# 1Coil.net
KiCad netlist of a schematic drawn in EAGLE
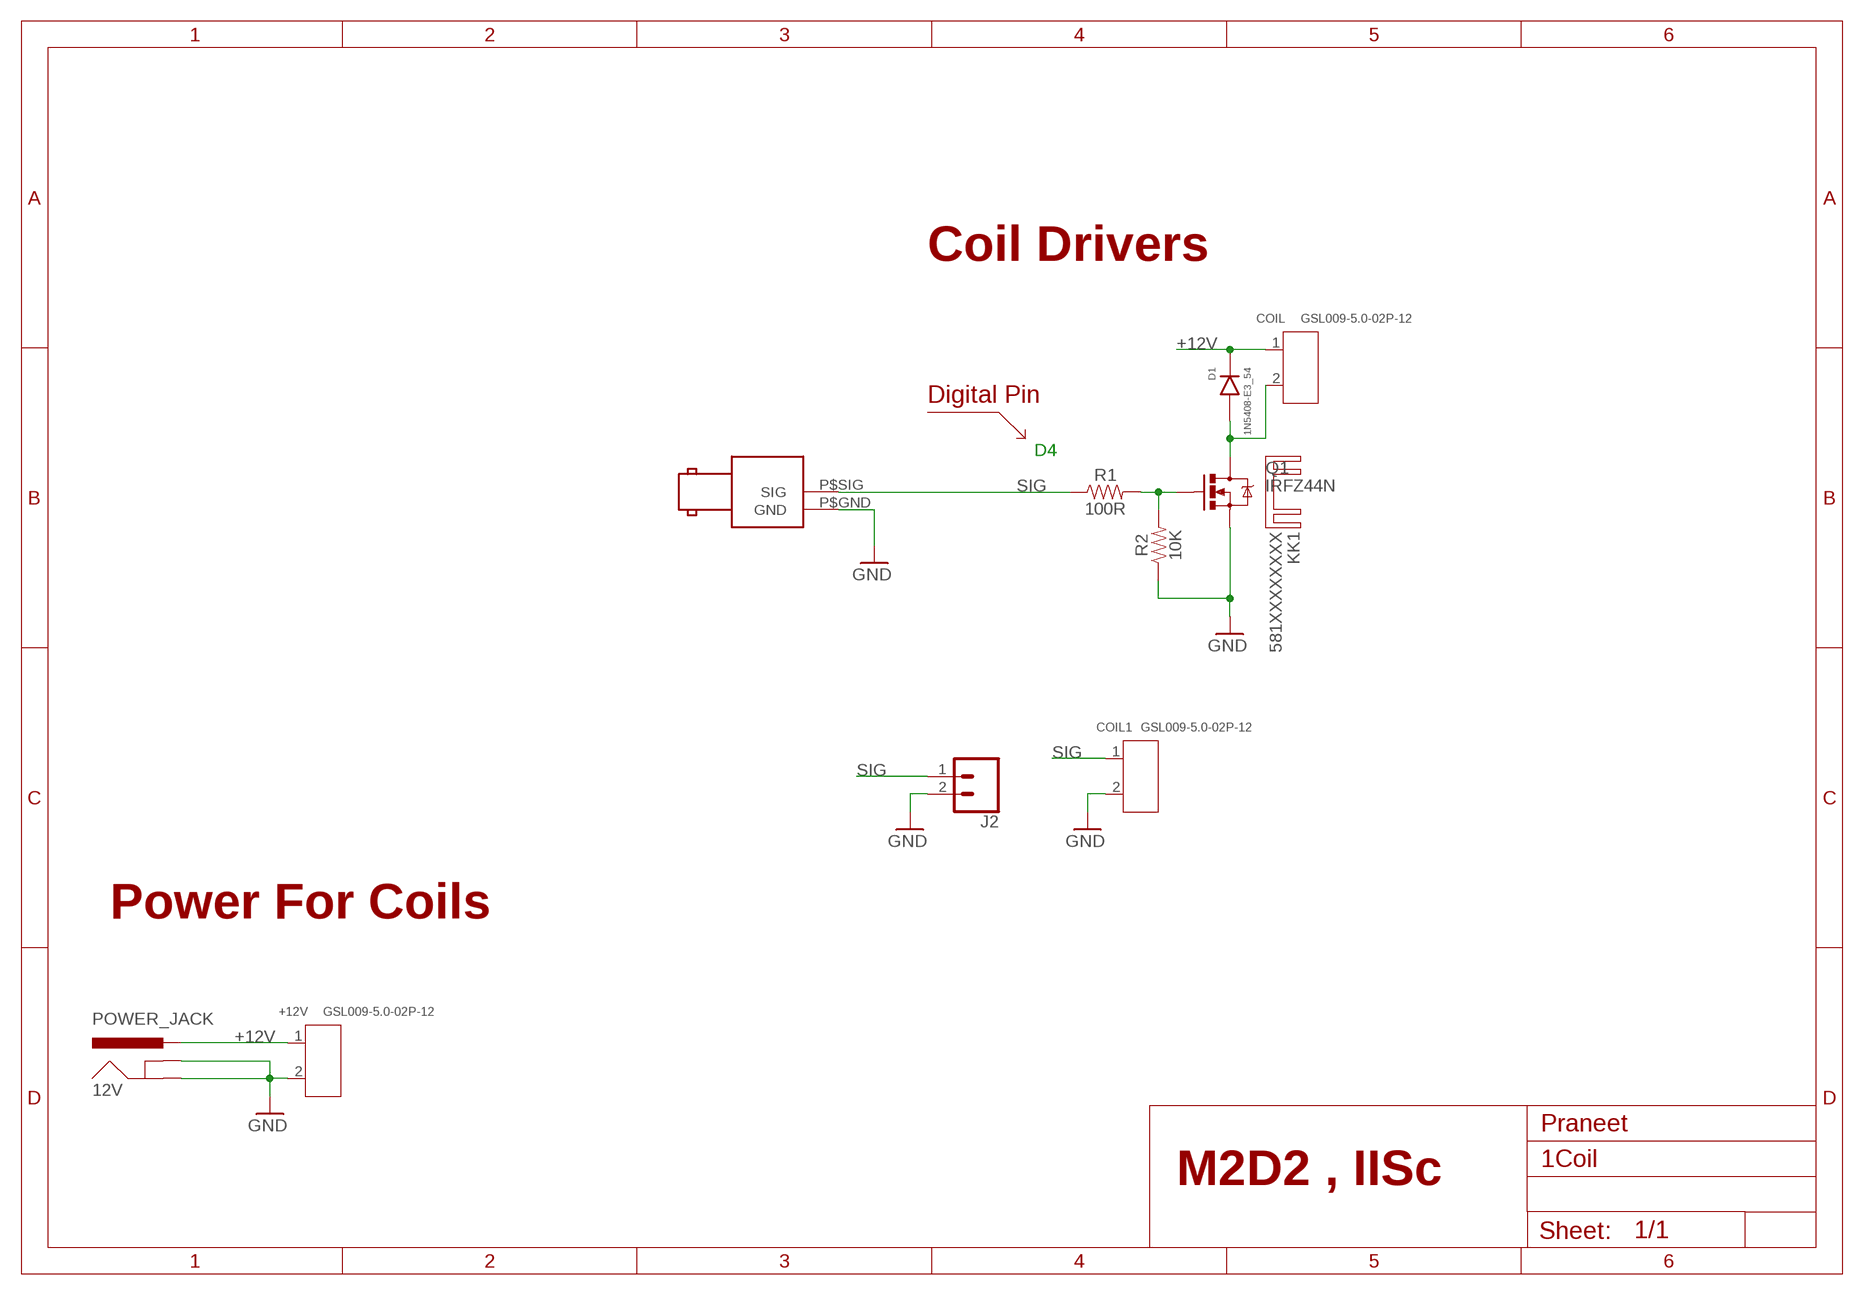
[diagram p0: schematic, sheet 1]

(export (version "E")
  (design (tool "Eeschema 10.0.6"))
  (components
    (comp (ref "+12V")
      (value "GSL009-5.0-02P-12")
      (footprint "eagle-import:H2-5.0-10.5X8.0MM")
      (libsource (lib "eagle-import") (part "SCREW-TERMINAL-BLUE(2P-5.0)"))
    )
    (comp (ref "12V")
      (value "POWER_JACK")
      (footprint "eagle-import:POWER_JACK_PTH")
      (libsource (lib "eagle-import") (part "POWER_JACK"))
    )
    (comp (ref "BNC")
      (value "BNC_RIGHT_ANGLE")
      (footprint "eagle-import:BNC_RIGHT_ANGLE")
      (libsource (lib "eagle-import") (part "BNC_RIGHT_ANGLE"))
    )
    (comp (ref "COIL")
      (value "GSL009-5.0-02P-12")
      (footprint "eagle-import:H2-5.0-10.5X8.0MM")
      (libsource (lib "eagle-import") (part "SCREW-TERMINAL-BLUE(2P-5.0)"))
    )
    (comp (ref "COIL1")
      (value "GSL009-5.0-02P-12")
      (footprint "eagle-import:H2-5.0-10.5X8.0MM")
      (libsource (lib "eagle-import") (part "SCREW-TERMINAL-BLUE(2P-5.0)"))
    )
    (comp (ref "D1")
      (value "1N5408-E3_54")
      (footprint "eagle-import:DIOAD2855W132L835D505")
      (fields
        (field (name "MANUFACTURER_PART_NUMBER") "1N5408-E3/54")
        (field (name "MOUSER_PART_NUMBER") "625-1N5408-E3")
        (field (name "RS_PART_NUMBER") "6289502P")
      )
      (libsource (lib "eagle-import") (part "1N5408-E3_54"))
    )
    (comp (ref "J2")
      (value "CONN_02POLAR")
      (footprint "eagle-import:MOLEX-1X2")
      (libsource (lib "eagle-import") (part "CONN_02POLAR"))
    )
    (comp (ref "KK1")
      (value "581XXXXXXXX")
      (footprint "eagle-import:581XXXXXXXX")
      (libsource (lib "eagle-import") (part "581XXXXXXXX"))
    )
    (comp (ref "Q1")
      (value "IRFZ44N")
      (footprint "eagle-import:TO-220")
      (fields (field (name "MF") "International Rectifier"))
      (libsource (lib "eagle-import") (part "IRFZ44N"))
    )
    (comp (ref "R1")
      (value "100R")
      (footprint "eagle-import:AXIAL-0.3")
      (libsource (lib "eagle-import") (part "RESISTORAXIAL-0.3"))
    )
    (comp (ref "R2")
      (value "10K")
      (footprint "eagle-import:AXIAL-0.3")
      (libsource (lib "eagle-import") (part "RESISTORAXIAL-0.3"))
    )
  )
  (nets
    (net (code "1") (name "/+12V") (class "Default")
      (node (ref "+12V") (pin "1") (pinfunction "1_1") (pintype "bidirectional"))
      (node (ref "12V") (pin "PWR") (pinfunction "PWR_PWR") (pintype "bidirectional"))
      (node (ref "COIL") (pin "1") (pinfunction "1_1") (pintype "bidirectional"))
      (node (ref "D1") (pin "1") (pinfunction "K_1") (pintype "bidirectional"))
    )
    (net (code "2") (name "/SIG") (class "Default")
      (node (ref "BNC") (pin "P$SIG") (pinfunction "SIG_P$SIG") (pintype "bidirectional"))
      (node (ref "COIL1") (pin "1") (pinfunction "1_1") (pintype "bidirectional"))
      (node (ref "J2") (pin "1") (pinfunction "1_1") (pintype "passive"))
      (node (ref "R1") (pin "P$1") (pinfunction "1_P$1") (pintype "passive"))
    )
    (net (code "3") (name "GND") (class "Default")
      (node (ref "+12V") (pin "2") (pinfunction "2_2") (pintype "bidirectional"))
      (node (ref "12V") (pin "GND") (pinfunction "GND_GND") (pintype "bidirectional"))
      (node (ref "12V") (pin "GNDBREAK") (pinfunction "GNDBREAK_GNDBREAK") (pintype "bidirectional"))
      (node (ref "BNC") (pin "P$GND") (pinfunction "GND_P$GND") (pintype "bidirectional"))
      (node (ref "COIL1") (pin "2") (pinfunction "2_2") (pintype "bidirectional"))
      (node (ref "J2") (pin "2") (pinfunction "2_2") (pintype "passive"))
      (node (ref "Q1") (pin "3") (pinfunction "S_3") (pintype "passive"))
      (node (ref "R2") (pin "P$1") (pinfunction "1_P$1") (pintype "passive"))
    )
    (net (code "4") (name "Net-(D1-A)") (class "Default")
      (node (ref "COIL") (pin "2") (pinfunction "2_2") (pintype "bidirectional"))
      (node (ref "D1") (pin "2") (pinfunction "A_2") (pintype "bidirectional"))
      (node (ref "Q1") (pin "2") (pinfunction "D_2") (pintype "passive"))
    )
    (net (code "5") (name "Net-(Q1-G)") (class "Default")
      (node (ref "Q1") (pin "1") (pinfunction "G_1") (pintype "passive"))
      (node (ref "R1") (pin "P$2") (pinfunction "2_P$2") (pintype "passive"))
      (node (ref "R2") (pin "P$2") (pinfunction "2_P$2") (pintype "passive"))
    )
  )
)
